# LilyPad-reed-v10.net
KiCad netlist of a schematic drawn in EAGLE
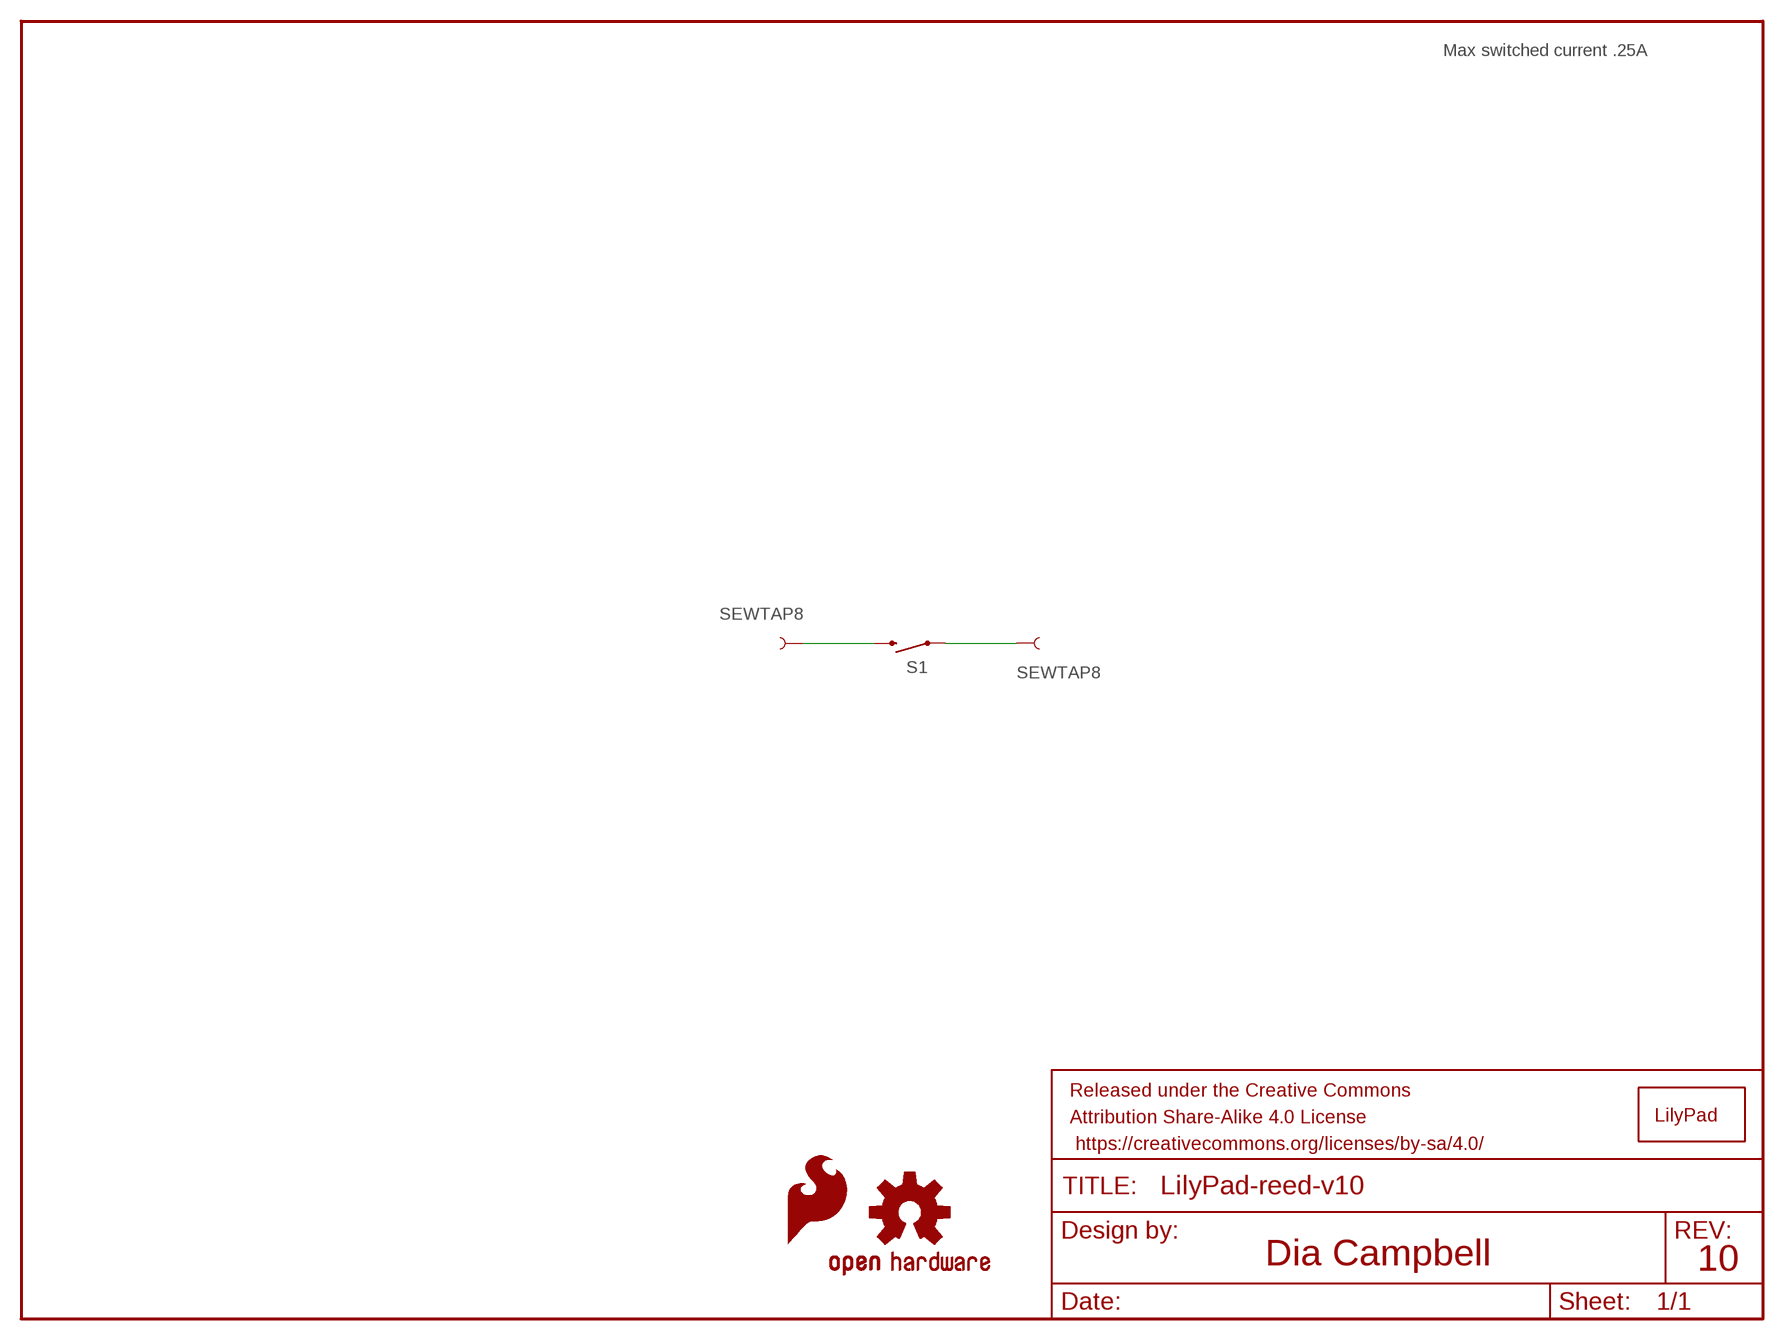
[diagram p0: schematic, sheet 1]

(export (version "E")
  (design (tool "Eeschema 10.0.6"))
  (components
    (comp (ref "FRAME1")
      (value "FRAME-LETTER")
      (footprint "eagle-import:CREATIVE_COMMONS")
      (fields (field (name "DESIGNER") "NAME"))
      (libsource (lib "eagle-import") (part "FRAME-LETTER"))
    )
    (comp (ref "LOGO1")
      (value "OSHW-LOGOS-COPPER")
      (footprint "eagle-import:OSHW-LOGO-S_COPPER")
      (libsource (lib "eagle-import") (part "OSHW-LOGOS-COPPER"))
    )
    (comp (ref "LOGO2")
      (value "SFE_LOGO_FLAME.1COP")
      (footprint "eagle-import:SFE_LOGO_FLAME_COPPER_.1")
      (libsource (lib "eagle-import") (part "SFE_LOGO_FLAME.1COP"))
    )
    (comp (ref "S1")
      (value "REED")
      (footprint "eagle-import:REED_SWITCH_PLASTIC")
      (libsource (lib "eagle-import") (part "SWITCH-MOMENTARY-2PTH_REED2"))
    )
    (comp (ref "SLIDEOFF")
      (value "SEWTAP8")
      (footprint "eagle-import:PETAL-MEDIUM-2SIDE")
      (libsource (lib "eagle-import") (part "SEWTAP8"))
    )
    (comp (ref "SLIDEON")
      (value "SEWTAP8")
      (footprint "eagle-import:PETAL-MEDIUM-2SIDE")
      (libsource (lib "eagle-import") (part "SEWTAP8"))
    )
    (comp (ref "U$1")
      (value "LOGO-LPLP")
      (footprint "eagle-import:LOGO-LILYPAD")
      (libsource (lib "eagle-import") (part "LOGO-LPLP"))
    )
  )
  (nets
    (net (code "1") (name "Net-(S1-1)") (class "Default")
      (node (ref "S1") (pin "P$1") (pinfunction "1_P$1") (pintype "passive"))
      (node (ref "SLIDEON") (pin "1") (pinfunction "1_1") (pintype "bidirectional"))
    )
    (net (code "2") (name "Net-(S1-2)") (class "Default")
      (node (ref "S1") (pin "P$2") (pinfunction "2_P$2") (pintype "passive"))
      (node (ref "SLIDEOFF") (pin "1") (pinfunction "1_1") (pintype "bidirectional"))
    )
  )
)
